# Main.net
KiCad netlist of a schematic drawn in Altium Designer
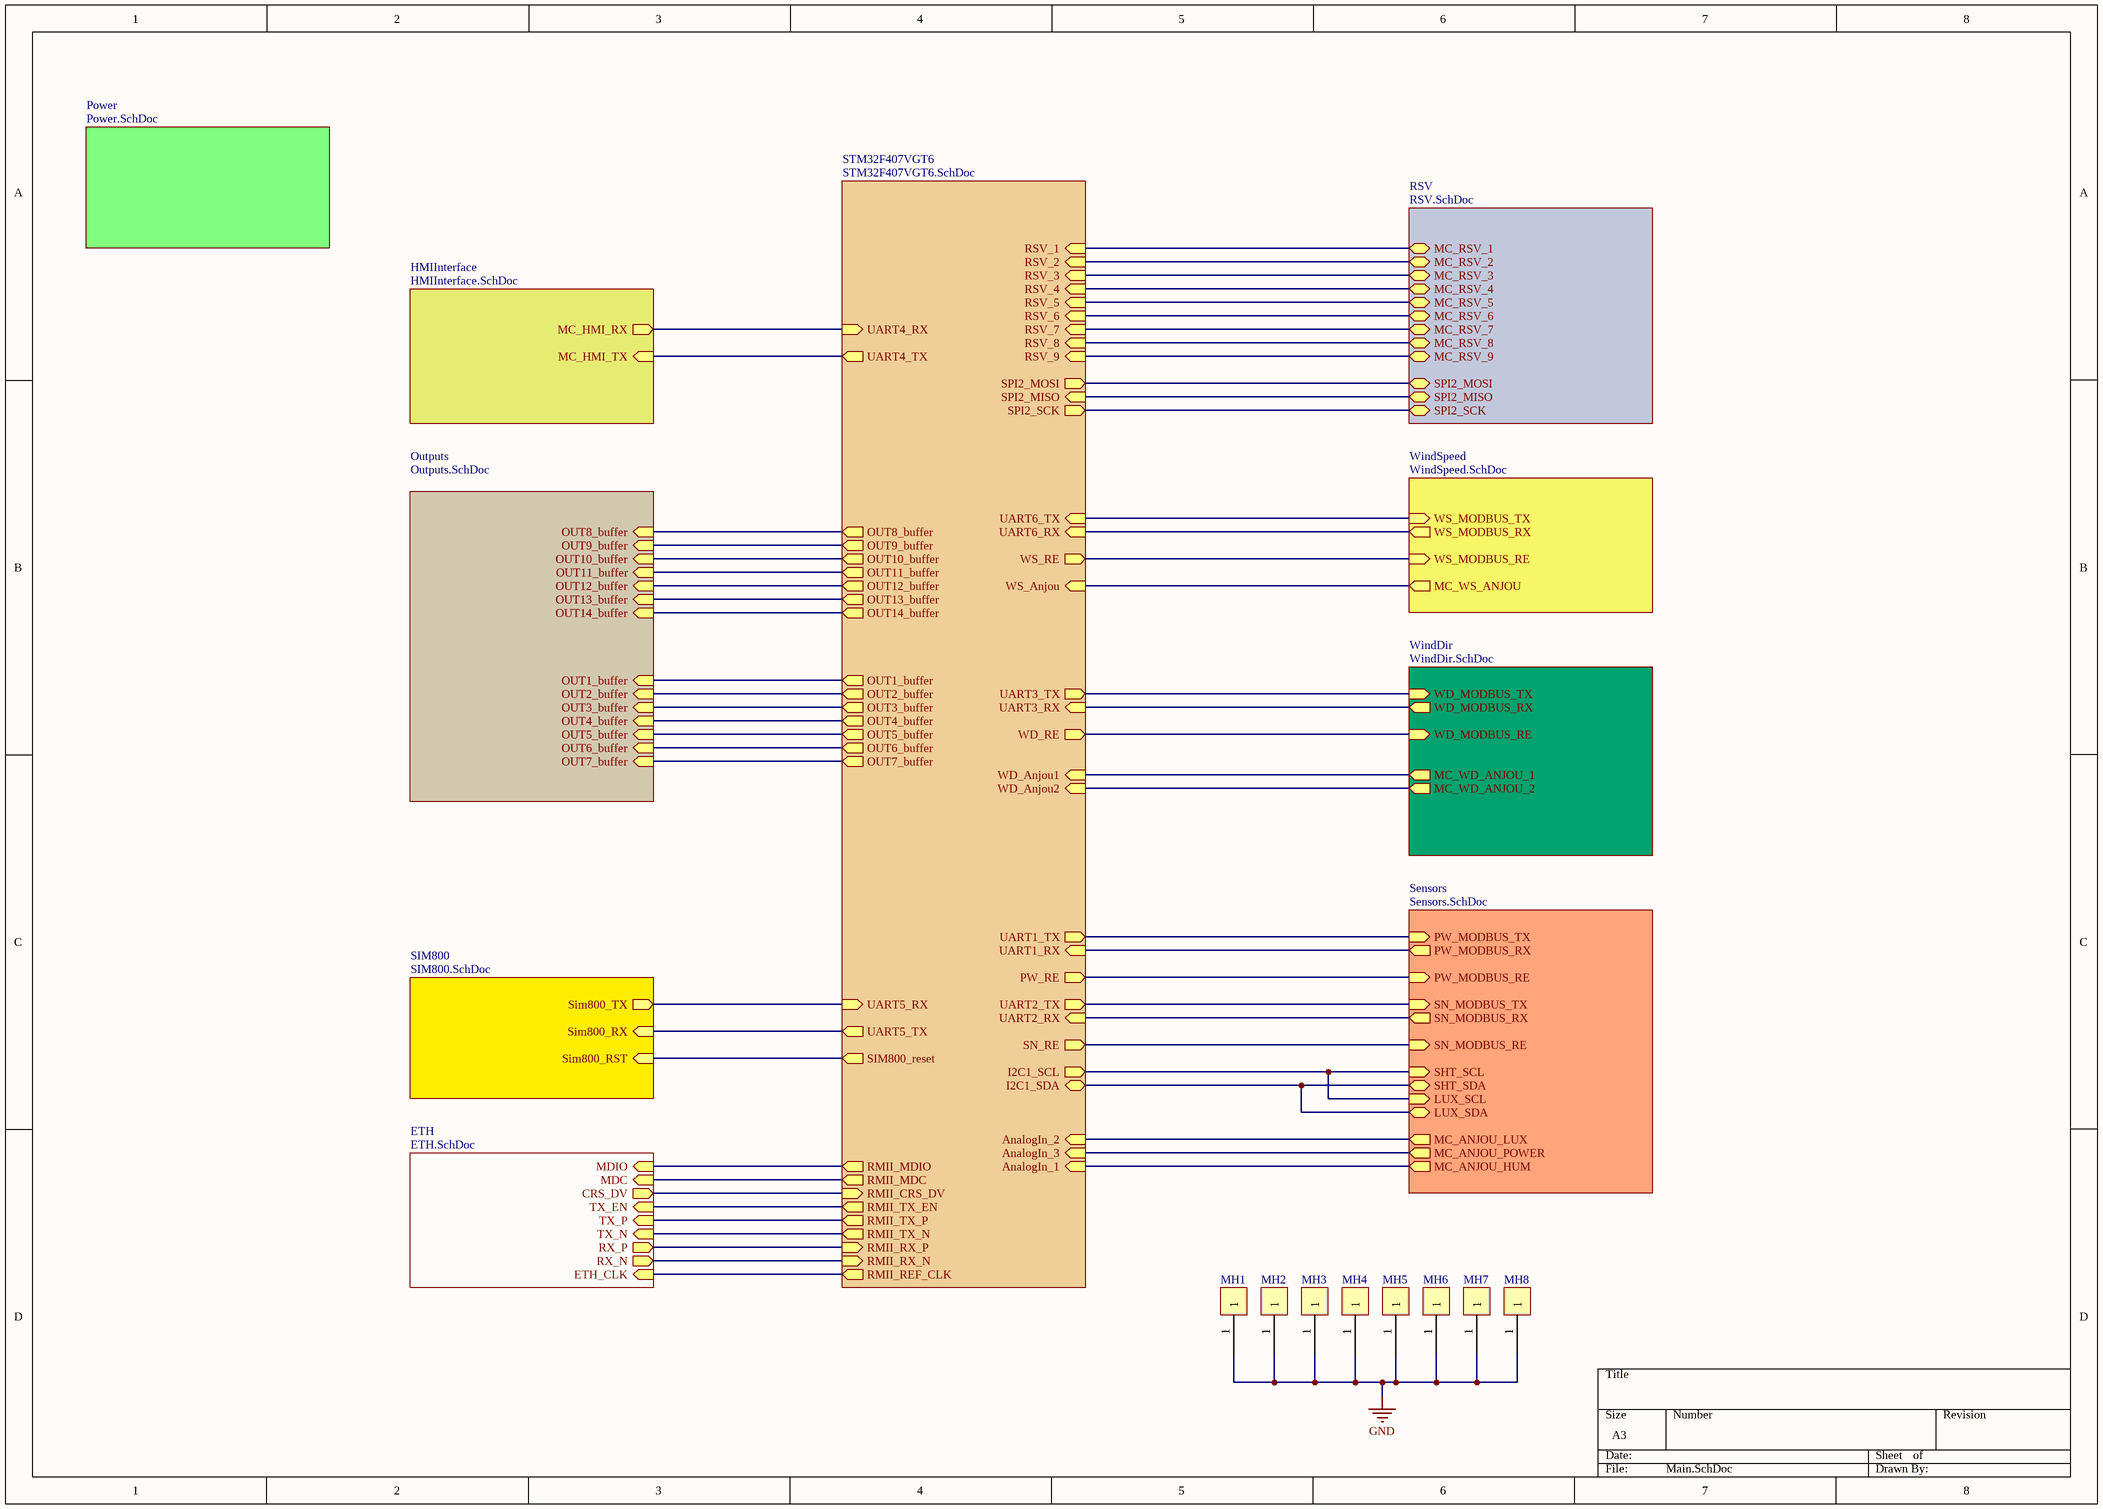
[diagram p0: Main.SchDoc]

(export (version "E")
  (design (tool "Eeschema 10.0.6"))
  (components
    (comp (ref "MH1") (value "HOLE_3mm") (footprint "Hole_3mm") (libsource (lib "AfraLIB") (part "HOLE_3mm")))
    (comp (ref "MH2") (value "HOLE_3mm") (footprint "Hole_3mm") (libsource (lib "AfraLIB") (part "HOLE_3mm")))
    (comp (ref "MH3") (value "HOLE_3mm") (footprint "Hole_3mm") (libsource (lib "AfraLIB") (part "HOLE_3mm")))
    (comp (ref "MH4") (value "HOLE_3mm") (footprint "Hole_3mm") (libsource (lib "AfraLIB") (part "HOLE_3mm")))
    (comp (ref "MH5") (value "HOLE_3mm") (footprint "Hole_3mm") (libsource (lib "AfraLIB") (part "HOLE_3mm")))
    (comp (ref "MH6") (value "HOLE_3mm") (footprint "Hole_3mm") (libsource (lib "AfraLIB") (part "HOLE_3mm")))
    (comp (ref "MH7") (value "HOLE_3mm") (footprint "Hole_3mm") (libsource (lib "AfraLIB") (part "HOLE_3mm")))
    (comp (ref "MH8") (value "HOLE_3mm") (footprint "Hole_3mm") (libsource (lib "AfraLIB") (part "HOLE_3mm")))
  )
  (nets
    (net (code "61") (name "GND") (class "Default")
      (node (ref "MH1") (pin "1") (pinfunction "1_1") (pintype "passive"))
      (node (ref "MH2") (pin "1") (pinfunction "1_1") (pintype "passive"))
      (node (ref "MH3") (pin "1") (pinfunction "1_1") (pintype "passive"))
      (node (ref "MH4") (pin "1") (pinfunction "1_1") (pintype "passive"))
      (node (ref "MH5") (pin "1") (pinfunction "1_1") (pintype "passive"))
      (node (ref "MH6") (pin "1") (pinfunction "1_1") (pintype "passive"))
      (node (ref "MH7") (pin "1") (pinfunction "1_1") (pintype "passive"))
      (node (ref "MH8") (pin "1") (pinfunction "1_1") (pintype "passive"))
    )
  )
)
